# Schematic_rangkaian_krsri.net
KiCad netlist of a schematic drawn in EAGLE
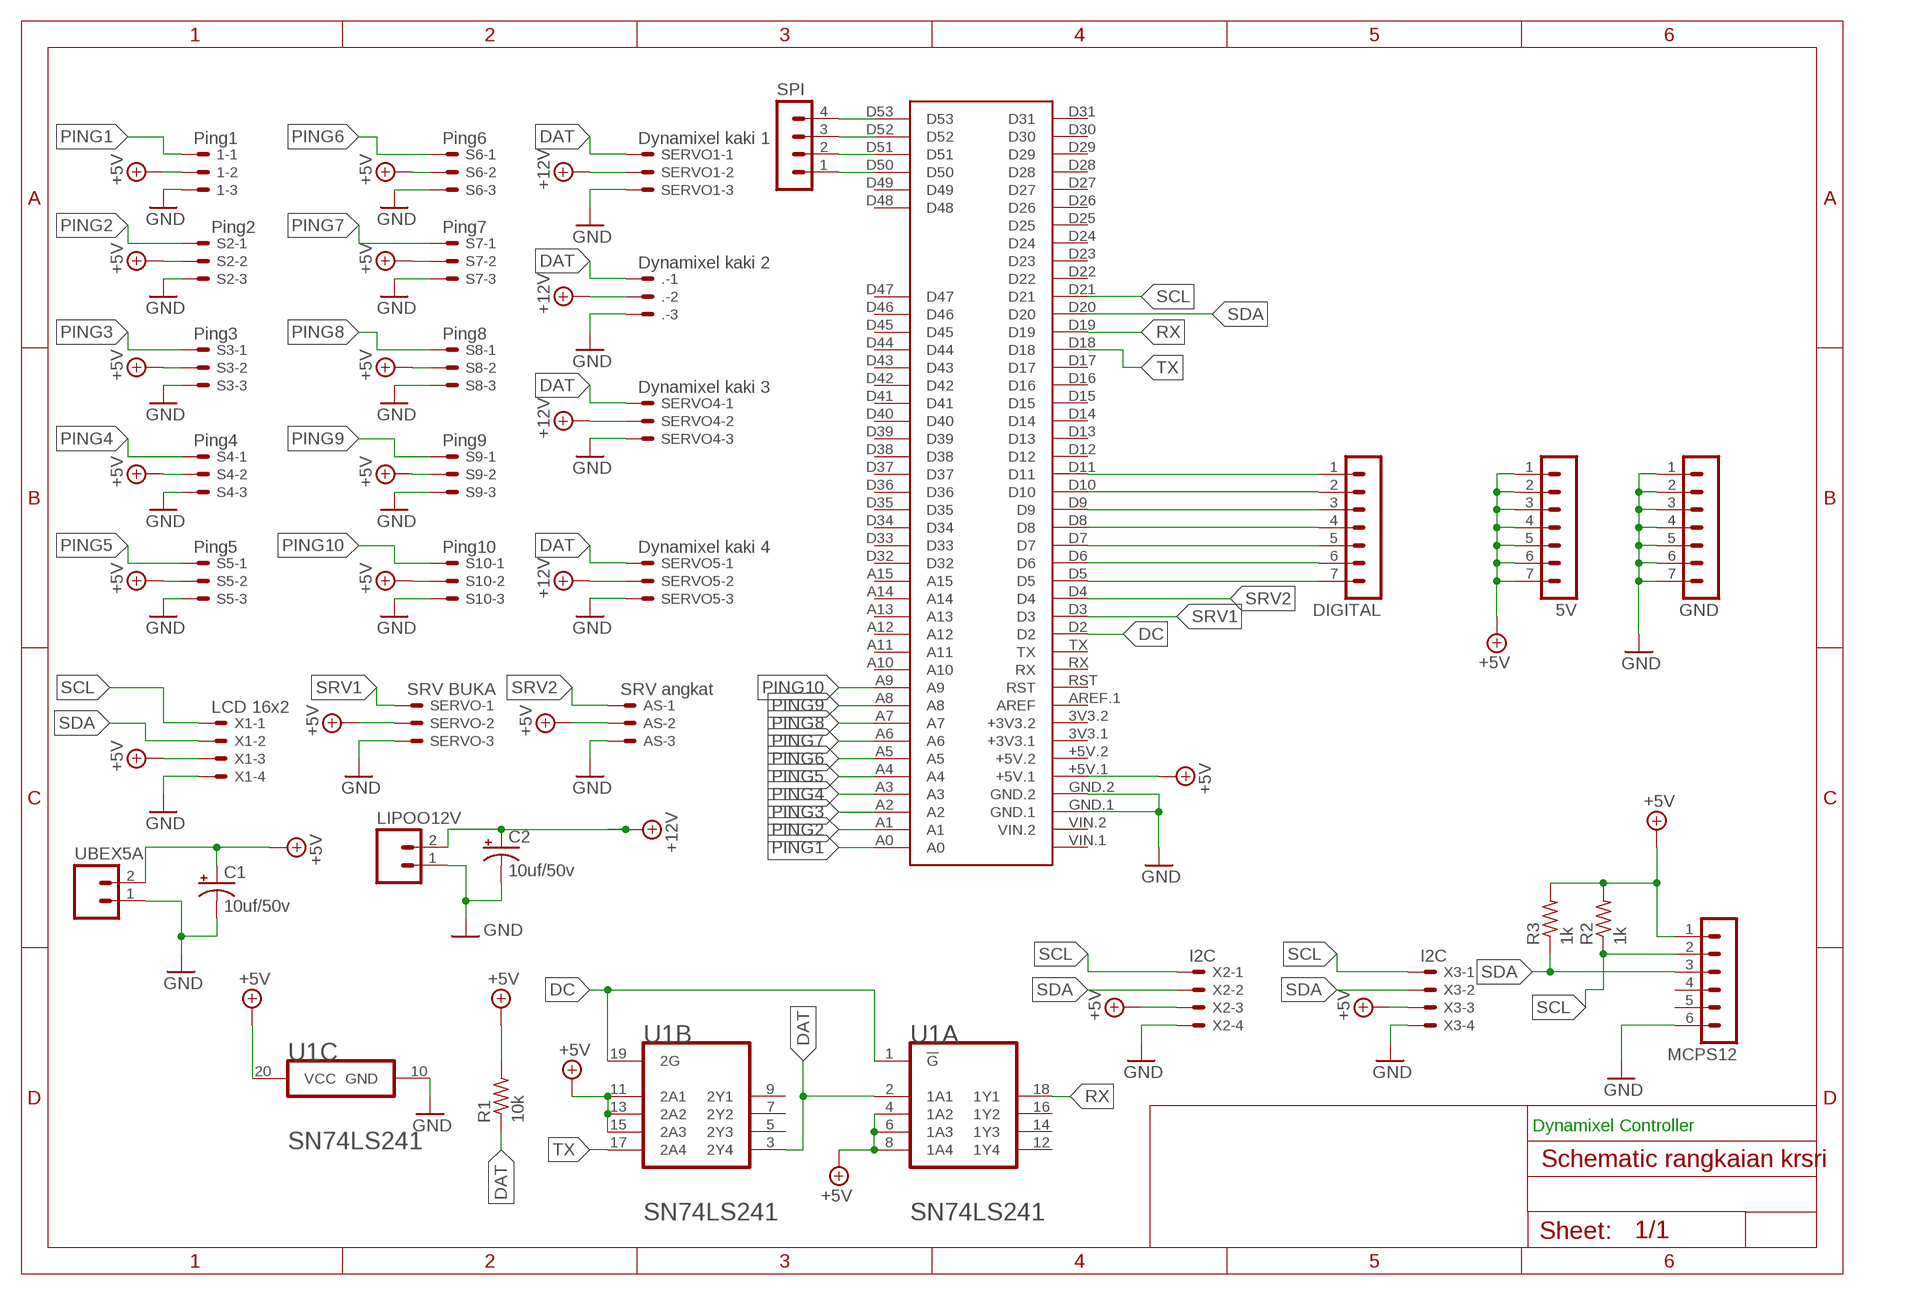
[diagram p0: schematic, sheet 1]

(export (version "E")
  (design (tool "Eeschema 10.0.6"))
  (components
    (comp (ref ".")
      (value "Dynamixel kaki 2")
      (footprint "eagle-import:22-23-2031")
      (fields (field (name "MF") "MOLEX") (field (name "MPN") "22-23-2031"))
      (libsource (lib "eagle-import") (part "22-23-2031"))
    )
    (comp (ref "1")
      (value "Ping1")
      (footprint "eagle-import:22-23-2031")
      (fields (field (name "MF") "MOLEX") (field (name "MPN") "22-23-2031"))
      (libsource (lib "eagle-import") (part "22-23-2031"))
    )
    (comp (ref "5V")
      (value "MA07-1")
      (footprint "eagle-import:MA07-1")
      (libsource (lib "eagle-import") (part "MA07-1"))
    )
    (comp (ref "AS")
      (value "SRV angkat")
      (footprint "eagle-import:22-23-2031")
      (fields (field (name "MF") "MOLEX") (field (name "MPN") "22-23-2031"))
      (libsource (lib "eagle-import") (part "22-23-2031"))
    )
    (comp (ref "C1")
      (value "10uf/50v")
      (footprint "eagle-import:E5-8,5")
      (libsource (lib "eagle-import") (part "CPOL-USE5-8.5"))
    )
    (comp (ref "C2")
      (value "10uf/50v")
      (footprint "eagle-import:E5-8,5")
      (libsource (lib "eagle-import") (part "CPOL-USE5-8.5"))
    )
    (comp (ref "DIGITAL")
      (value "MA07-1")
      (footprint "eagle-import:MA07-1")
      (libsource (lib "eagle-import") (part "MA07-1"))
    )
    (comp (ref "GND")
      (value "MA07-1")
      (footprint "eagle-import:MA07-1")
      (libsource (lib "eagle-import") (part "MA07-1"))
    )
    (comp (ref "LIPOO12V")
      (value "M02")
      (footprint "eagle-import:02P")
      (libsource (lib "eagle-import") (part "M02"))
    )
    (comp (ref "MCPS12")
      (value "MA06-1")
      (footprint "eagle-import:MA06-1")
      (libsource (lib "eagle-import") (part "MA06-1"))
    )
    (comp (ref "R1")
      (value "10k")
      (footprint "eagle-import:0204_7")
      (libsource (lib "eagle-import") (part "R-US_0204/7"))
    )
    (comp (ref "R2")
      (value "1k")
      (footprint "eagle-import:0204_7")
      (libsource (lib "eagle-import") (part "R-US_0204/7"))
    )
    (comp (ref "R3")
      (value "1k")
      (footprint "eagle-import:0204_7")
      (libsource (lib "eagle-import") (part "R-US_0204/7"))
    )
    (comp (ref "S2")
      (value "Ping2")
      (footprint "eagle-import:22-23-2031")
      (fields (field (name "MF") "MOLEX") (field (name "MPN") "22-23-2031"))
      (libsource (lib "eagle-import") (part "22-23-2031"))
    )
    (comp (ref "S3")
      (value "Ping3")
      (footprint "eagle-import:22-23-2031")
      (fields (field (name "MF") "MOLEX") (field (name "MPN") "22-23-2031"))
      (libsource (lib "eagle-import") (part "22-23-2031"))
    )
    (comp (ref "S4")
      (value "Ping4")
      (footprint "eagle-import:22-23-2031")
      (fields (field (name "MF") "MOLEX") (field (name "MPN") "22-23-2031"))
      (libsource (lib "eagle-import") (part "22-23-2031"))
    )
    (comp (ref "S5")
      (value "Ping5")
      (footprint "eagle-import:22-23-2031")
      (fields (field (name "MF") "MOLEX") (field (name "MPN") "22-23-2031"))
      (libsource (lib "eagle-import") (part "22-23-2031"))
    )
    (comp (ref "S6")
      (value "Ping6")
      (footprint "eagle-import:22-23-2031")
      (fields (field (name "MF") "MOLEX") (field (name "MPN") "22-23-2031"))
      (libsource (lib "eagle-import") (part "22-23-2031"))
    )
    (comp (ref "S7")
      (value "Ping7")
      (footprint "eagle-import:22-23-2031")
      (fields (field (name "MF") "MOLEX") (field (name "MPN") "22-23-2031"))
      (libsource (lib "eagle-import") (part "22-23-2031"))
    )
    (comp (ref "S8")
      (value "Ping8")
      (footprint "eagle-import:22-23-2031")
      (fields (field (name "MF") "MOLEX") (field (name "MPN") "22-23-2031"))
      (libsource (lib "eagle-import") (part "22-23-2031"))
    )
    (comp (ref "S9")
      (value "Ping9")
      (footprint "eagle-import:22-23-2031")
      (fields (field (name "MF") "MOLEX") (field (name "MPN") "22-23-2031"))
      (libsource (lib "eagle-import") (part "22-23-2031"))
    )
    (comp (ref "S10")
      (value "Ping10")
      (footprint "eagle-import:22-23-2031")
      (fields (field (name "MF") "MOLEX") (field (name "MPN") "22-23-2031"))
      (libsource (lib "eagle-import") (part "22-23-2031"))
    )
    (comp (ref "SERVO")
      (value "SRV BUKA")
      (footprint "eagle-import:22-23-2031")
      (fields (field (name "MF") "MOLEX") (field (name "MPN") "22-23-2031"))
      (libsource (lib "eagle-import") (part "22-23-2031"))
    )
    (comp (ref "SERVO1")
      (value "Dynamixel kaki 1")
      (footprint "eagle-import:22-23-2031")
      (fields (field (name "MF") "MOLEX") (field (name "MPN") "22-23-2031"))
      (libsource (lib "eagle-import") (part "22-23-2031"))
    )
    (comp (ref "SERVO4")
      (value "Dynamixel kaki 3")
      (footprint "eagle-import:22-23-2031")
      (fields (field (name "MF") "MOLEX") (field (name "MPN") "22-23-2031"))
      (libsource (lib "eagle-import") (part "22-23-2031"))
    )
    (comp (ref "SERVO5")
      (value "Dynamixel kaki 4")
      (footprint "eagle-import:22-23-2031")
      (fields (field (name "MF") "MOLEX") (field (name "MPN") "22-23-2031"))
      (libsource (lib "eagle-import") (part "22-23-2031"))
    )
    (comp (ref "SPI")
      (value "MA04-1")
      (footprint "eagle-import:MA04-1")
      (libsource (lib "eagle-import") (part "MA04-1"))
    )
    (comp (ref "U$1")
      (value "MEGA2560_MIKRO")
      (footprint "eagle-import:MEGA2560_MIKRO")
      (libsource (lib "eagle-import") (part "MEGA2560_MIKRO"))
    )
    (comp (ref "U1")
      (value "TEXAS_INSTRUMENTS_SN74LS241TEXAS_INSTRUMENTS_SN74LS241_0_0")
      (footprint "eagle-import:TEXAS_INSTRUMENTS_SN74LS241_0")
      (fields (field (name "MF") "Texas Instruments") (field (name "MPN") "SN74LS241"))
      (libsource (lib "eagle-import") (part "TEXAS_INSTRUMENTS_SN74LS241TEXAS_INSTRUMENTS_SN74LS241_0_0"))
    )
    (comp (ref "UBEX5A")
      (value "M02")
      (footprint "eagle-import:02P")
      (libsource (lib "eagle-import") (part "M02"))
    )
    (comp (ref "X1")
      (value "LCD 16x2")
      (footprint "eagle-import:22-23-2041")
      (fields (field (name "MF") "MOLEX") (field (name "MPN") "22-23-2041"))
      (libsource (lib "eagle-import") (part "22-23-2041"))
    )
    (comp (ref "X2")
      (value "I2C")
      (footprint "eagle-import:22-23-2041")
      (fields (field (name "MF") "MOLEX") (field (name "MPN") "22-23-2041"))
      (libsource (lib "eagle-import") (part "22-23-2041"))
    )
    (comp (ref "X3")
      (value "I2C")
      (footprint "eagle-import:22-23-2041")
      (fields (field (name "MF") "MOLEX") (field (name "MPN") "22-23-2041"))
      (libsource (lib "eagle-import") (part "22-23-2041"))
    )
  )
  (nets
    (net (code "1") (name "+5V") (class "Default")
      (node (ref "1") (pin "2") (pinfunction "S_2") (pintype "passive"))
      (node (ref "5V") (pin "1") (pinfunction "1_1") (pintype "passive"))
      (node (ref "5V") (pin "2") (pinfunction "2_2") (pintype "passive"))
      (node (ref "5V") (pin "3") (pinfunction "3_3") (pintype "passive"))
      (node (ref "5V") (pin "4") (pinfunction "4_4") (pintype "passive"))
      (node (ref "5V") (pin "5") (pinfunction "5_5") (pintype "passive"))
      (node (ref "5V") (pin "6") (pinfunction "6_6") (pintype "passive"))
      (node (ref "5V") (pin "7") (pinfunction "7_7") (pintype "passive"))
      (node (ref "AS") (pin "2") (pinfunction "S_2") (pintype "passive"))
      (node (ref "C1") (pin "+") (pinfunction "+_+") (pintype "passive"))
      (node (ref "MCPS12") (pin "1") (pinfunction "1_1") (pintype "passive"))
      (node (ref "R1") (pin "2") (pinfunction "2_2") (pintype "passive"))
      (node (ref "R2") (pin "2") (pinfunction "2_2") (pintype "passive"))
      (node (ref "R3") (pin "2") (pinfunction "2_2") (pintype "passive"))
      (node (ref "S10") (pin "2") (pinfunction "S_2") (pintype "passive"))
      (node (ref "S2") (pin "2") (pinfunction "S_2") (pintype "passive"))
      (node (ref "S3") (pin "2") (pinfunction "S_2") (pintype "passive"))
      (node (ref "S4") (pin "2") (pinfunction "S_2") (pintype "passive"))
      (node (ref "S5") (pin "2") (pinfunction "S_2") (pintype "passive"))
      (node (ref "S6") (pin "2") (pinfunction "S_2") (pintype "passive"))
      (node (ref "S7") (pin "2") (pinfunction "S_2") (pintype "passive"))
      (node (ref "S8") (pin "2") (pinfunction "S_2") (pintype "passive"))
      (node (ref "S9") (pin "2") (pinfunction "S_2") (pintype "passive"))
      (node (ref "SERVO") (pin "2") (pinfunction "S_2") (pintype "passive"))
      (node (ref "U$1") (pin "+5V.1") (pinfunction "+5V.1_+5V.1") (pintype "bidirectional"))
      (node (ref "U1") (pin "11") (pinfunction "2A1_11") (pintype "input"))
      (node (ref "U1") (pin "13") (pinfunction "2A2_13") (pintype "input"))
      (node (ref "U1") (pin "15") (pinfunction "2A3_15") (pintype "input"))
      (node (ref "U1") (pin "20") (pinfunction "VCC_20") (pintype "power_in"))
      (node (ref "U1") (pin "4") (pinfunction "1A2_4") (pintype "input"))
      (node (ref "U1") (pin "6") (pinfunction "1A3_6") (pintype "input"))
      (node (ref "U1") (pin "8") (pinfunction "1A4_8") (pintype "input"))
      (node (ref "UBEX5A") (pin "2") (pinfunction "2_2") (pintype "passive"))
      (node (ref "X1") (pin "3") (pinfunction "S_3") (pintype "passive"))
      (node (ref "X2") (pin "3") (pinfunction "S_3") (pintype "passive"))
      (node (ref "X3") (pin "3") (pinfunction "S_3") (pintype "passive"))
    )
    (net (code "2") (name "+12V") (class "Default")
      (node (ref ".") (pin "2") (pinfunction "S_2") (pintype "passive"))
      (node (ref "C2") (pin "+") (pinfunction "+_+") (pintype "passive"))
      (node (ref "LIPOO12V") (pin "2") (pinfunction "2_2") (pintype "passive"))
      (node (ref "SERVO1") (pin "2") (pinfunction "S_2") (pintype "passive"))
      (node (ref "SERVO4") (pin "2") (pinfunction "S_2") (pintype "passive"))
      (node (ref "SERVO5") (pin "2") (pinfunction "S_2") (pintype "passive"))
    )
    (net (code "3") (name "DAT") (class "Default")
      (node (ref ".") (pin "1") (pinfunction "S_1") (pintype "passive"))
      (node (ref "R1") (pin "1") (pinfunction "1_1") (pintype "passive"))
      (node (ref "SERVO1") (pin "1") (pinfunction "S_1") (pintype "passive"))
      (node (ref "SERVO4") (pin "1") (pinfunction "S_1") (pintype "passive"))
      (node (ref "SERVO5") (pin "1") (pinfunction "S_1") (pintype "passive"))
      (node (ref "U1") (pin "2") (pinfunction "1A1_2") (pintype "input"))
      (node (ref "U1") (pin "3") (pinfunction "2Y4_3") (pintype "tri_state"))
    )
    (net (code "4") (name "DC") (class "Default")
      (node (ref "U$1") (pin "D2") (pinfunction "D2_D2") (pintype "bidirectional"))
      (node (ref "U1") (pin "1") (pinfunction "~{G}_1") (pintype "input"))
      (node (ref "U1") (pin "19") (pinfunction "2G_19") (pintype "input"))
    )
    (net (code "5") (name "GND") (class "Default")
      (node (ref ".") (pin "3") (pinfunction "S_3") (pintype "passive"))
      (node (ref "1") (pin "3") (pinfunction "S_3") (pintype "passive"))
      (node (ref "AS") (pin "3") (pinfunction "S_3") (pintype "passive"))
      (node (ref "C1") (pin "-") (pinfunction "-_-") (pintype "passive"))
      (node (ref "C2") (pin "-") (pinfunction "-_-") (pintype "passive"))
      (node (ref "GND") (pin "1") (pinfunction "1_1") (pintype "passive"))
      (node (ref "GND") (pin "2") (pinfunction "2_2") (pintype "passive"))
      (node (ref "GND") (pin "3") (pinfunction "3_3") (pintype "passive"))
      (node (ref "GND") (pin "4") (pinfunction "4_4") (pintype "passive"))
      (node (ref "GND") (pin "5") (pinfunction "5_5") (pintype "passive"))
      (node (ref "GND") (pin "6") (pinfunction "6_6") (pintype "passive"))
      (node (ref "GND") (pin "7") (pinfunction "7_7") (pintype "passive"))
      (node (ref "LIPOO12V") (pin "1") (pinfunction "1_1") (pintype "passive"))
      (node (ref "MCPS12") (pin "6") (pinfunction "6_6") (pintype "passive"))
      (node (ref "S10") (pin "3") (pinfunction "S_3") (pintype "passive"))
      (node (ref "S2") (pin "3") (pinfunction "S_3") (pintype "passive"))
      (node (ref "S3") (pin "3") (pinfunction "S_3") (pintype "passive"))
      (node (ref "S4") (pin "3") (pinfunction "S_3") (pintype "passive"))
      (node (ref "S5") (pin "3") (pinfunction "S_3") (pintype "passive"))
      (node (ref "S6") (pin "3") (pinfunction "S_3") (pintype "passive"))
      (node (ref "S7") (pin "3") (pinfunction "S_3") (pintype "passive"))
      (node (ref "S8") (pin "3") (pinfunction "S_3") (pintype "passive"))
      (node (ref "S9") (pin "3") (pinfunction "S_3") (pintype "passive"))
      (node (ref "SERVO") (pin "3") (pinfunction "S_3") (pintype "passive"))
      (node (ref "SERVO1") (pin "3") (pinfunction "S_3") (pintype "passive"))
      (node (ref "SERVO4") (pin "3") (pinfunction "S_3") (pintype "passive"))
      (node (ref "SERVO5") (pin "3") (pinfunction "S_3") (pintype "passive"))
      (node (ref "U$1") (pin "GND.1") (pinfunction "GND.1_GND.1") (pintype "bidirectional"))
      (node (ref "U$1") (pin "GND.2") (pinfunction "GND.2_GND.2") (pintype "bidirectional"))
      (node (ref "U1") (pin "10") (pinfunction "GND_10") (pintype "power_in"))
      (node (ref "UBEX5A") (pin "1") (pinfunction "1_1") (pintype "passive"))
      (node (ref "X1") (pin "4") (pinfunction "S_4") (pintype "passive"))
      (node (ref "X2") (pin "4") (pinfunction "S_4") (pintype "passive"))
      (node (ref "X3") (pin "4") (pinfunction "S_4") (pintype "passive"))
    )
    (net (code "6") (name "Net-(DIGITAL-Pad1)") (class "Default")
      (node (ref "DIGITAL") (pin "1") (pinfunction "1_1") (pintype "passive"))
      (node (ref "U$1") (pin "D11") (pinfunction "D11_D11") (pintype "bidirectional"))
    )
    (net (code "7") (name "Net-(DIGITAL-Pad2)") (class "Default")
      (node (ref "DIGITAL") (pin "2") (pinfunction "2_2") (pintype "passive"))
      (node (ref "U$1") (pin "D10") (pinfunction "D10_D10") (pintype "bidirectional"))
    )
    (net (code "8") (name "Net-(DIGITAL-Pad3)") (class "Default")
      (node (ref "DIGITAL") (pin "3") (pinfunction "3_3") (pintype "passive"))
      (node (ref "U$1") (pin "D9") (pinfunction "D9_D9") (pintype "bidirectional"))
    )
    (net (code "9") (name "Net-(DIGITAL-Pad4)") (class "Default")
      (node (ref "DIGITAL") (pin "4") (pinfunction "4_4") (pintype "passive"))
      (node (ref "U$1") (pin "D8") (pinfunction "D8_D8") (pintype "bidirectional"))
    )
    (net (code "10") (name "Net-(DIGITAL-Pad5)") (class "Default")
      (node (ref "DIGITAL") (pin "5") (pinfunction "5_5") (pintype "passive"))
      (node (ref "U$1") (pin "D7") (pinfunction "D7_D7") (pintype "bidirectional"))
    )
    (net (code "11") (name "Net-(DIGITAL-Pad6)") (class "Default")
      (node (ref "DIGITAL") (pin "6") (pinfunction "6_6") (pintype "passive"))
      (node (ref "U$1") (pin "D6") (pinfunction "D6_D6") (pintype "bidirectional"))
    )
    (net (code "12") (name "Net-(DIGITAL-Pad7)") (class "Default")
      (node (ref "DIGITAL") (pin "7") (pinfunction "7_7") (pintype "passive"))
      (node (ref "U$1") (pin "D5") (pinfunction "D5_D5") (pintype "bidirectional"))
    )
    (net (code "13") (name "Net-(SPI-Pad1)") (class "Default")
      (node (ref "SPI") (pin "1") (pinfunction "1_1") (pintype "passive"))
      (node (ref "U$1") (pin "D50") (pinfunction "D50_D50") (pintype "bidirectional"))
    )
    (net (code "14") (name "Net-(SPI-Pad2)") (class "Default")
      (node (ref "SPI") (pin "2") (pinfunction "2_2") (pintype "passive"))
      (node (ref "U$1") (pin "D51") (pinfunction "D51_D51") (pintype "bidirectional"))
    )
    (net (code "15") (name "Net-(SPI-Pad3)") (class "Default")
      (node (ref "SPI") (pin "3") (pinfunction "3_3") (pintype "passive"))
      (node (ref "U$1") (pin "D52") (pinfunction "D52_D52") (pintype "bidirectional"))
    )
    (net (code "16") (name "Net-(SPI-Pad4)") (class "Default")
      (node (ref "SPI") (pin "4") (pinfunction "4_4") (pintype "passive"))
      (node (ref "U$1") (pin "D53") (pinfunction "D53_D53") (pintype "bidirectional"))
    )
    (net (code "17") (name "PING1") (class "Default")
      (node (ref "1") (pin "1") (pinfunction "S_1") (pintype "passive"))
      (node (ref "U$1") (pin "A0") (pinfunction "A0_A0") (pintype "bidirectional"))
    )
    (net (code "18") (name "PING2") (class "Default")
      (node (ref "S2") (pin "1") (pinfunction "S_1") (pintype "passive"))
      (node (ref "U$1") (pin "A1") (pinfunction "A1_A1") (pintype "bidirectional"))
    )
    (net (code "19") (name "PING3") (class "Default")
      (node (ref "S3") (pin "1") (pinfunction "S_1") (pintype "passive"))
      (node (ref "U$1") (pin "A2") (pinfunction "A2_A2") (pintype "bidirectional"))
    )
    (net (code "20") (name "PING4") (class "Default")
      (node (ref "S4") (pin "1") (pinfunction "S_1") (pintype "passive"))
      (node (ref "U$1") (pin "A3") (pinfunction "A3_A3") (pintype "bidirectional"))
    )
    (net (code "21") (name "PING5") (class "Default")
      (node (ref "S5") (pin "1") (pinfunction "S_1") (pintype "passive"))
      (node (ref "U$1") (pin "A4") (pinfunction "A4_A4") (pintype "bidirectional"))
    )
    (net (code "22") (name "PING6") (class "Default")
      (node (ref "S6") (pin "1") (pinfunction "S_1") (pintype "passive"))
      (node (ref "U$1") (pin "A5") (pinfunction "A5_A5") (pintype "bidirectional"))
    )
    (net (code "23") (name "PING7") (class "Default")
      (node (ref "S7") (pin "1") (pinfunction "S_1") (pintype "passive"))
      (node (ref "U$1") (pin "A6") (pinfunction "A6_A6") (pintype "bidirectional"))
    )
    (net (code "24") (name "PING8") (class "Default")
      (node (ref "S8") (pin "1") (pinfunction "S_1") (pintype "passive"))
      (node (ref "U$1") (pin "A7") (pinfunction "A7_A7") (pintype "bidirectional"))
    )
    (net (code "25") (name "PING9") (class "Default")
      (node (ref "S9") (pin "1") (pinfunction "S_1") (pintype "passive"))
      (node (ref "U$1") (pin "A8") (pinfunction "A8_A8") (pintype "bidirectional"))
    )
    (net (code "26") (name "PING10") (class "Default")
      (node (ref "S10") (pin "1") (pinfunction "S_1") (pintype "passive"))
      (node (ref "U$1") (pin "A9") (pinfunction "A9_A9") (pintype "bidirectional"))
    )
    (net (code "27") (name "RX") (class "Default")
      (node (ref "U$1") (pin "D19") (pinfunction "D19_D19") (pintype "bidirectional"))
      (node (ref "U1") (pin "18") (pinfunction "1Y1_18") (pintype "tri_state"))
    )
    (net (code "28") (name "SCL") (class "Default")
      (node (ref "MCPS12") (pin "2") (pinfunction "2_2") (pintype "passive"))
      (node (ref "R2") (pin "1") (pinfunction "1_1") (pintype "passive"))
      (node (ref "U$1") (pin "D21") (pinfunction "D21_D21") (pintype "bidirectional"))
      (node (ref "X1") (pin "1") (pinfunction "S_1") (pintype "passive"))
      (node (ref "X2") (pin "1") (pinfunction "S_1") (pintype "passive"))
      (node (ref "X3") (pin "1") (pinfunction "S_1") (pintype "passive"))
    )
    (net (code "29") (name "SDA") (class "Default")
      (node (ref "MCPS12") (pin "3") (pinfunction "3_3") (pintype "passive"))
      (node (ref "R3") (pin "1") (pinfunction "1_1") (pintype "passive"))
      (node (ref "U$1") (pin "D20") (pinfunction "D20_D20") (pintype "bidirectional"))
      (node (ref "X1") (pin "2") (pinfunction "S_2") (pintype "passive"))
      (node (ref "X2") (pin "2") (pinfunction "S_2") (pintype "passive"))
      (node (ref "X3") (pin "2") (pinfunction "S_2") (pintype "passive"))
    )
    (net (code "30") (name "SRV1") (class "Default")
      (node (ref "SERVO") (pin "1") (pinfunction "S_1") (pintype "passive"))
      (node (ref "U$1") (pin "D3") (pinfunction "D3_D3") (pintype "bidirectional"))
    )
    (net (code "31") (name "SRV2") (class "Default")
      (node (ref "AS") (pin "1") (pinfunction "S_1") (pintype "passive"))
      (node (ref "U$1") (pin "D4") (pinfunction "D4_D4") (pintype "bidirectional"))
    )
    (net (code "32") (name "TX") (class "Default")
      (node (ref "U$1") (pin "D18") (pinfunction "D18_D18") (pintype "bidirectional"))
      (node (ref "U1") (pin "17") (pinfunction "2A4_17") (pintype "input"))
    )
    (net (code "33") (name "unconnected-(MCPS12-Pad4)") (class "Default")
      (node (ref "MCPS12") (pin "4") (pinfunction "4_4") (pintype "passive"))
    )
    (net (code "34") (name "unconnected-(MCPS12-Pad5)") (class "Default")
      (node (ref "MCPS12") (pin "5") (pinfunction "5_5") (pintype "passive"))
    )
    (net (code "35") (name "unconnected-(U$1-+3V3.1-Pad3V3.1)") (class "Default")
      (node (ref "U$1") (pin "3V3.1") (pinfunction "+3V3.1_3V3.1") (pintype "bidirectional"))
    )
    (net (code "36") (name "unconnected-(U$1-+3V3.2-Pad3V3.2)") (class "Default")
      (node (ref "U$1") (pin "3V3.2") (pinfunction "+3V3.2_3V3.2") (pintype "bidirectional"))
    )
    (net (code "37") (name "unconnected-(U$1-AREF-PadAREF.1)") (class "Default")
      (node (ref "U$1") (pin "AREF.1") (pinfunction "AREF_AREF.1") (pintype "bidirectional"))
    )
    (net (code "38") (name "unconnected-(U$1-Pad+5V.2)") (class "Default")
      (node (ref "U$1") (pin "+5V.2") (pinfunction "+5V.2_+5V.2") (pintype "bidirectional"))
    )
    (net (code "39") (name "unconnected-(U$1-PadA10)") (class "Default")
      (node (ref "U$1") (pin "A10") (pinfunction "A10_A10") (pintype "bidirectional"))
    )
    (net (code "40") (name "unconnected-(U$1-PadA11)") (class "Default")
      (node (ref "U$1") (pin "A11") (pinfunction "A11_A11") (pintype "bidirectional"))
    )
    (net (code "41") (name "unconnected-(U$1-PadA12)") (class "Default")
      (node (ref "U$1") (pin "A12") (pinfunction "A12_A12") (pintype "bidirectional"))
    )
    (net (code "42") (name "unconnected-(U$1-PadA13)") (class "Default")
      (node (ref "U$1") (pin "A13") (pinfunction "A13_A13") (pintype "bidirectional"))
    )
    (net (code "43") (name "unconnected-(U$1-PadA14)") (class "Default")
      (node (ref "U$1") (pin "A14") (pinfunction "A14_A14") (pintype "bidirectional"))
    )
    (net (code "44") (name "unconnected-(U$1-PadA15)") (class "Default")
      (node (ref "U$1") (pin "A15") (pinfunction "A15_A15") (pintype "bidirectional"))
    )
    (net (code "45") (name "unconnected-(U$1-PadD12)") (class "Default")
      (node (ref "U$1") (pin "D12") (pinfunction "D12_D12") (pintype "bidirectional"))
    )
    (net (code "46") (name "unconnected-(U$1-PadD13)") (class "Default")
      (node (ref "U$1") (pin "D13") (pinfunction "D13_D13") (pintype "bidirectional"))
    )
    (net (code "47") (name "unconnected-(U$1-PadD14)") (class "Default")
      (node (ref "U$1") (pin "D14") (pinfunction "D14_D14") (pintype "bidirectional"))
    )
    (net (code "48") (name "unconnected-(U$1-PadD15)") (class "Default")
      (node (ref "U$1") (pin "D15") (pinfunction "D15_D15") (pintype "bidirectional"))
    )
    (net (code "49") (name "unconnected-(U$1-PadD16)") (class "Default")
      (node (ref "U$1") (pin "D16") (pinfunction "D16_D16") (pintype "bidirectional"))
    )
    (net (code "50") (name "unconnected-(U$1-PadD17)") (class "Default")
      (node (ref "U$1") (pin "D17") (pinfunction "D17_D17") (pintype "bidirectional"))
    )
    (net (code "51") (name "unconnected-(U$1-PadD22)") (class "Default")
      (node (ref "U$1") (pin "D22") (pinfunction "D22_D22") (pintype "bidirectional"))
    )
    (net (code "52") (name "unconnected-(U$1-PadD23)") (class "Default")
      (node (ref "U$1") (pin "D23") (pinfunction "D23_D23") (pintype "bidirectional"))
    )
    (net (code "53") (name "unconnected-(U$1-PadD24)") (class "Default")
      (node (ref "U$1") (pin "D24") (pinfunction "D24_D24") (pintype "bidirectional"))
    )
    (net (code "54") (name "unconnected-(U$1-PadD25)") (class "Default")
      (node (ref "U$1") (pin "D25") (pinfunction "D25_D25") (pintype "bidirectional"))
    )
    (net (code "55") (name "unconnected-(U$1-PadD26)") (class "Default")
      (node (ref "U$1") (pin "D26") (pinfunction "D26_D26") (pintype "bidirectional"))
    )
    (net (code "56") (name "unconnected-(U$1-PadD27)") (class "Default")
      (node (ref "U$1") (pin "D27") (pinfunction "D27_D27") (pintype "bidirectional"))
    )
    (net (code "57") (name "unconnected-(U$1-PadD28)") (class "Default")
      (node (ref "U$1") (pin "D28") (pinfunction "D28_D28") (pintype "bidirectional"))
    )
    (net (code "58") (name "unconnected-(U$1-PadD29)") (class "Default")
      (node (ref "U$1") (pin "D29") (pinfunction "D29_D29") (pintype "bidirectional"))
    )
    (net (code "59") (name "unconnected-(U$1-PadD30)") (class "Default")
      (node (ref "U$1") (pin "D30") (pinfunction "D30_D30") (pintype "bidirectional"))
    )
    (net (code "60") (name "unconnected-(U$1-PadD31)") (class "Default")
      (node (ref "U$1") (pin "D31") (pinfunction "D31_D31") (pintype "bidirectional"))
    )
    (net (code "61") (name "unconnected-(U$1-PadD32)") (class "Default")
      (node (ref "U$1") (pin "D32") (pinfunction "D32_D32") (pintype "bidirectional"))
    )
    (net (code "62") (name "unconnected-(U$1-PadD33)") (class "Default")
      (node (ref "U$1") (pin "D33") (pinfunction "D33_D33") (pintype "bidirectional"))
    )
    (net (code "63") (name "unconnected-(U$1-PadD34)") (class "Default")
      (node (ref "U$1") (pin "D34") (pinfunction "D34_D34") (pintype "bidirectional"))
    )
    (net (code "64") (name "unconnected-(U$1-PadD35)") (class "Default")
      (node (ref "U$1") (pin "D35") (pinfunction "D35_D35") (pintype "bidirectional"))
    )
    (net (code "65") (name "unconnected-(U$1-PadD36)") (class "Default")
      (node (ref "U$1") (pin "D36") (pinfunction "D36_D36") (pintype "bidirectional"))
    )
    (net (code "66") (name "unconnected-(U$1-PadD37)") (class "Default")
      (node (ref "U$1") (pin "D37") (pinfunction "D37_D37") (pintype "bidirectional"))
    )
    (net (code "67") (name "unconnected-(U$1-PadD38)") (class "Default")
      (node (ref "U$1") (pin "D38") (pinfunction "D38_D38") (pintype "bidirectional"))
    )
    (net (code "68") (name "unconnected-(U$1-PadD39)") (class "Default")
      (node (ref "U$1") (pin "D39") (pinfunction "D39_D39") (pintype "bidirectional"))
    )
    (net (code "69") (name "unconnected-(U$1-PadD40)") (class "Default")
      (node (ref "U$1") (pin "D40") (pinfunction "D40_D40") (pintype "bidirectional"))
    )
    (net (code "70") (name "unconnected-(U$1-PadD41)") (class "Default")
      (node (ref "U$1") (pin "D41") (pinfunction "D41_D41") (pintype "bidirectional"))
    )
    (net (code "71") (name "unconnected-(U$1-PadD42)") (class "Default")
      (node (ref "U$1") (pin "D42") (pinfunction "D42_D42") (pintype "bidirectional"))
    )
    (net (code "72") (name "unconnected-(U$1-PadD43)") (class "Default")
      (node (ref "U$1") (pin "D43") (pinfunction "D43_D43") (pintype "bidirectional"))
    )
    (net (code "73") (name "unconnected-(U$1-PadD44)") (class "Default")
      (node (ref "U$1") (pin "D44") (pinfunction "D44_D44") (pintype "bidirectional"))
    )
    (net (code "74") (name "unconnected-(U$1-PadD45)") (class "Default")
      (node (ref "U$1") (pin "D45") (pinfunction "D45_D45") (pintype "bidirectional"))
    )
    (net (code "75") (name "unconnected-(U$1-PadD46)") (class "Default")
      (node (ref "U$1") (pin "D46") (pinfunction "D46_D46") (pintype "bidirectional"))
    )
    (net (code "76") (name "unconnected-(U$1-PadD47)") (class "Default")
      (node (ref "U$1") (pin "D47") (pinfunction "D47_D47") (pintype "bidirectional"))
    )
    (net (code "77") (name "unconnected-(U$1-PadD48)") (class "Default")
      (node (ref "U$1") (pin "D48") (pinfunction "D48_D48") (pintype "bidirectional"))
    )
    (net (code "78") (name "unconnected-(U$1-PadD49)") (class "Default")
      (node (ref "U$1") (pin "D49") (pinfunction "D49_D49") (pintype "bidirectional"))
    )
    (net (code "79") (name "unconnected-(U$1-PadRST)") (class "Default")
      (node (ref "U$1") (pin "RST") (pinfunction "RST_RST") (pintype "bidirectional"))
    )
    (net (code "80") (name "unconnected-(U$1-PadRX)") (class "Default")
      (node (ref "U$1") (pin "RX") (pinfunction "RX_RX") (pintype "bidirectional"))
    )
    (net (code "81") (name "unconnected-(U$1-PadTX)") (class "Default")
      (node (ref "U$1") (pin "TX") (pinfunction "TX_TX") (pintype "bidirectional"))
    )
    (net (code "82") (name "unconnected-(U$1-PadVIN.1)") (class "Default")
      (node (ref "U$1") (pin "VIN.1") (pinfunction "VIN.1_VIN.1") (pintype "bidirectional"))
    )
    (net (code "83") (name "unconnected-(U$1-PadVIN.2)") (class "Default")
      (node (ref "U$1") (pin "VIN.2") (pinfunction "VIN.2_VIN.2") (pintype "bidirectional"))
    )
    (net (code "84") (name "unconnected-(U1A-1Y2-Pad16)") (class "Default")
      (node (ref "U1") (pin "16") (pinfunction "1Y2_16") (pintype "tri_state"))
    )
    (net (code "85") (name "unconnected-(U1A-1Y3-Pad14)") (class "Default")
      (node (ref "U1") (pin "14") (pinfunction "1Y3_14") (pintype "tri_state"))
    )
    (net (code "86") (name "unconnected-(U1A-1Y4-Pad12)") (class "Default")
      (node (ref "U1") (pin "12") (pinfunction "1Y4_12") (pintype "tri_state"))
    )
    (net (code "87") (name "unconnected-(U1B-2Y1-Pad9)") (class "Default")
      (node (ref "U1") (pin "9") (pinfunction "2Y1_9") (pintype "tri_state"))
    )
    (net (code "88") (name "unconnected-(U1B-2Y2-Pad7)") (class "Default")
      (node (ref "U1") (pin "7") (pinfunction "2Y2_7") (pintype "tri_state"))
    )
    (net (code "89") (name "unconnected-(U1B-2Y3-Pad5)") (class "Default")
      (node (ref "U1") (pin "5") (pinfunction "2Y3_5") (pintype "tri_state"))
    )
  )
)
